# PCIe_1x.net
KiCad netlist of a schematic drawn in Altium Designer
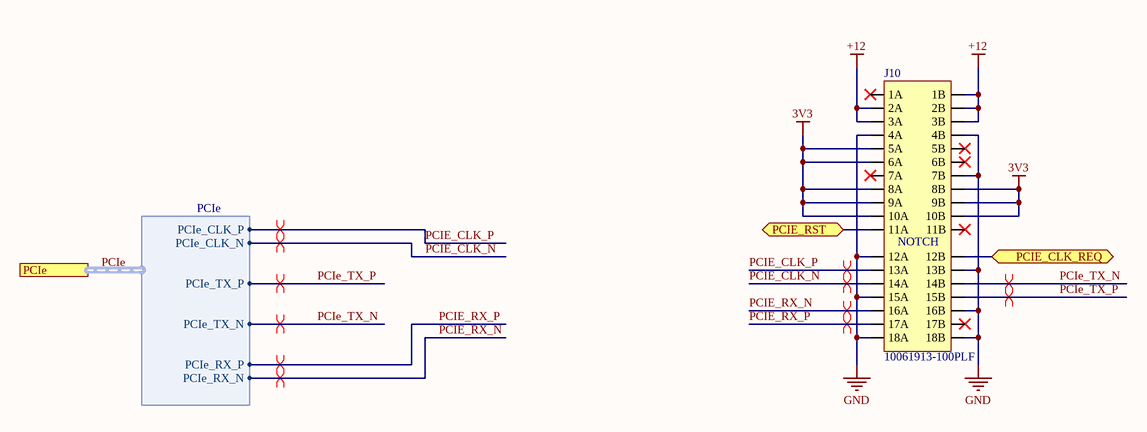
[diagram p0: PCIe_1x.SchDoc]

(export (version "E")
  (design (tool "Eeschema 10.0.6"))
  (components
    (comp (ref "J10")
      (value "10061913-100PLF")
      (footprint "AMPHENOL_10061913")
      (description "PCIe x1 Socket, 36-Pos, SMD, Amphenol")
      (fields (field (name "PART NUMBER") "CONN-00124") (field (name "MANUFACTURER") "Amphenol"))
      (libsource (lib "Connectors$") (part "CONN-00124"))
    )
  )
  (nets
    (net (code "2") (name "+12") (class "Default")
      (node (ref "J10") (pin "1B") (pinfunction "1B_1B") (pintype "passive"))
      (node (ref "J10") (pin "2A") (pinfunction "2A_2A") (pintype "passive"))
      (node (ref "J10") (pin "2B") (pinfunction "2B_2B") (pintype "passive"))
      (node (ref "J10") (pin "3A") (pinfunction "3A_3A") (pintype "passive"))
      (node (ref "J10") (pin "3B") (pinfunction "3B_3B") (pintype "passive"))
    )
    (net (code "3") (name "/PCIE_CLK_N") (class "Default")
      (node (ref "J10") (pin "14A") (pinfunction "14A_14A") (pintype "passive"))
    )
    (net (code "4") (name "/PCIE_CLK_P") (class "Default")
      (node (ref "J10") (pin "13A") (pinfunction "13A_13A") (pintype "passive"))
    )
    (net (code "5") (name "/PCIE_CLK_REQ") (class "Default")
      (node (ref "J10") (pin "12A") (pinfunction "12B_12A") (pintype "passive"))
    )
    (net (code "6") (name "/PCIE_RST") (class "Default")
      (node (ref "J10") (pin "11A") (pinfunction "11A_11A") (pintype "passive"))
    )
    (net (code "7") (name "/PCIE_RX_N") (class "Default")
      (node (ref "J10") (pin "16A") (pinfunction "16A_16A") (pintype "passive"))
    )
    (net (code "8") (name "/PCIE_RX_P") (class "Default")
      (node (ref "J10") (pin "17A") (pinfunction "17A_17A") (pintype "passive"))
    )
    (net (code "9") (name "/PCIe_TX_N") (class "Default")
      (node (ref "J10") (pin "14B") (pinfunction "14B_14B") (pintype "passive"))
    )
    (net (code "10") (name "/PCIe_TX_P") (class "Default")
      (node (ref "J10") (pin "15B") (pinfunction "15B_15B") (pintype "passive"))
    )
    (net (code "12") (name "3V3") (class "Default")
      (node (ref "J10") (pin "10A") (pinfunction "10A_10A") (pintype "passive"))
      (node (ref "J10") (pin "10B") (pinfunction "10B_10B") (pintype "passive"))
      (node (ref "J10") (pin "5A") (pinfunction "5A_5A") (pintype "passive"))
      (node (ref "J10") (pin "6A") (pinfunction "6A_6A") (pintype "passive"))
      (node (ref "J10") (pin "8A") (pinfunction "8A_8A") (pintype "passive"))
      (node (ref "J10") (pin "8B") (pinfunction "8B_8B") (pintype "passive"))
      (node (ref "J10") (pin "9A") (pinfunction "9A_9A") (pintype "passive"))
      (node (ref "J10") (pin "9B") (pinfunction "9B_9B") (pintype "passive"))
    )
    (net (code "13") (name "GND") (class "Default")
      (node (ref "J10") (pin "12A") (pinfunction "12A_12A") (pintype "passive"))
      (node (ref "J10") (pin "13B") (pinfunction "13B_13B") (pintype "passive"))
      (node (ref "J10") (pin "15A") (pinfunction "15A_15A") (pintype "passive"))
      (node (ref "J10") (pin "16B") (pinfunction "16B_16B") (pintype "passive"))
      (node (ref "J10") (pin "18A") (pinfunction "18A_18A") (pintype "passive"))
      (node (ref "J10") (pin "18B") (pinfunction "18B_18B") (pintype "passive"))
      (node (ref "J10") (pin "4A") (pinfunction "4A_4A") (pintype "passive"))
      (node (ref "J10") (pin "4B") (pinfunction "4B_4B") (pintype "passive"))
      (node (ref "J10") (pin "7B") (pinfunction "7B_7B") (pintype "passive"))
    )
    (net (code "14") (name "unconnected-(J10-Pad1A)") (class "Default")
      (node (ref "J10") (pin "1A") (pinfunction "1A_1A") (pintype "passive+no_connect"))
    )
    (net (code "15") (name "unconnected-(J10-Pad5B)") (class "Default")
      (node (ref "J10") (pin "5B") (pinfunction "5B_5B") (pintype "passive+no_connect"))
    )
    (net (code "16") (name "unconnected-(J10-Pad6B)") (class "Default")
      (node (ref "J10") (pin "6B") (pinfunction "6B_6B") (pintype "passive+no_connect"))
    )
    (net (code "17") (name "unconnected-(J10-Pad7A)") (class "Default")
      (node (ref "J10") (pin "7A") (pinfunction "7A_7A") (pintype "passive+no_connect"))
    )
    (net (code "18") (name "unconnected-(J10-Pad11B)") (class "Default")
      (node (ref "J10") (pin "11B") (pinfunction "11B_11B") (pintype "passive+no_connect"))
    )
    (net (code "19") (name "unconnected-(J10-Pad17B)") (class "Default")
      (node (ref "J10") (pin "17B") (pinfunction "17B_17B") (pintype "passive+no_connect"))
    )
  )
)
